# SeriesSwitch.net
KiCad netlist of a schematic drawn in Altium Designer
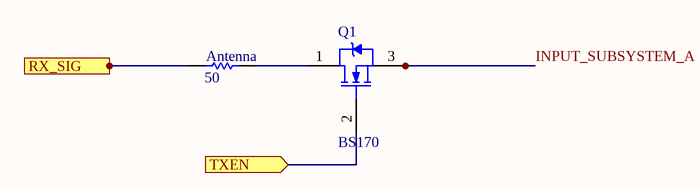
[diagram p0: SeriesSwitch.SchDoc]

(export (version "E")
  (design (tool "Eeschema 10.0.6"))
  (components
    (comp (ref "Antenna")
      (value "50")
      (description "Resistor")
      (libsource (lib "Simulation Generic Components") (part "Resistor"))
    )
    (comp (ref "Q1")
      (value "BS170")
      (footprint "ONSC-TO-92-3-29-11")
      (description "Small Signal MOSFET, 500 mA, 60 V, N-Channel, 3-Pin TO-92, Bulk Box")
      (fields (field (name "MANUFACTURER") "On Semiconductor"))
      (libsource (lib "Altium Content Vault") (part "ONSC-NMOS-D1G2S3-3"))
    )
  )
  (nets
    (net (code "1") (name "/INPUT_SUBSYSTEM_A") (class "Default")
      (node (ref "Q1") (pin "3") (pinfunction "S_3") (pintype "passive"))
    )
    (net (code "2") (name "/RX_SIG") (class "Default")
      (node (ref "Antenna") (pin "1") (pinfunction "1_1") (pintype "passive"))
    )
    (net (code "3") (name "/TXEN") (class "Default")
      (node (ref "Q1") (pin "2") (pinfunction "G_2") (pintype "passive"))
    )
    (net (code "4") (name "Net-(Q1-D)") (class "Default")
      (node (ref "Antenna") (pin "2") (pinfunction "2_2") (pintype "passive"))
      (node (ref "Q1") (pin "1") (pinfunction "D_1") (pintype "passive"))
    )
  )
)
